# LCD.net
KiCad netlist of a schematic drawn in Altium Designer
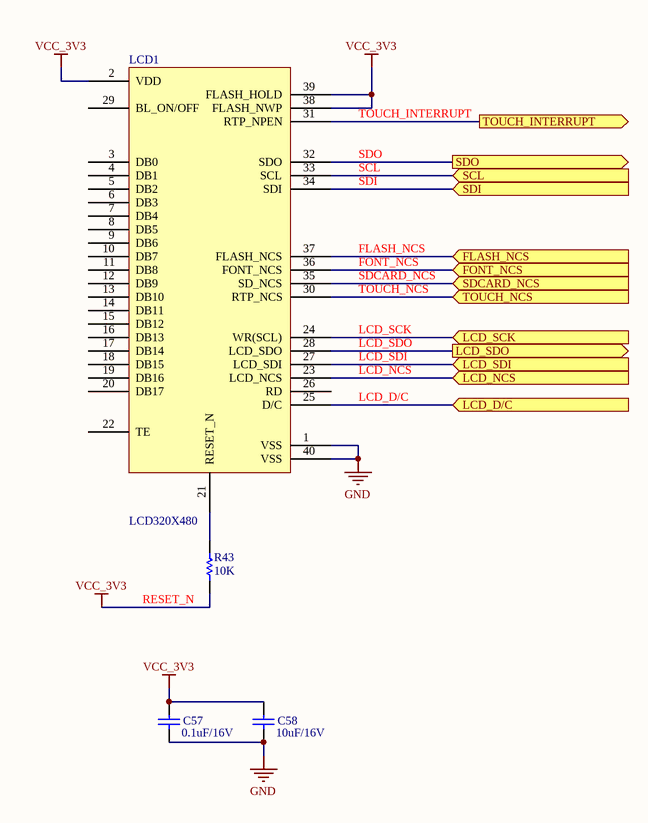
[diagram p0: LCD.SchDoc]

(export (version "E")
  (design (tool "Eeschema 10.0.6"))
  (components
    (comp (ref "C57")
      (value "0.1uF/16V")
      (footprint "RAD-0.3")
      (description "Capacitor")
      (fields (field (name "PUBLISHER") "Altium Limited"))
      (libsource (lib "Miscellaneous Devices") (part "Cap"))
    )
    (comp (ref "C58")
      (value "10uF/16V")
      (footprint "RAD-0.3")
      (description "Capacitor")
      (fields (field (name "PUBLISHER") "Altium Limited"))
      (libsource (lib "Miscellaneous Devices") (part "Cap"))
    )
    (comp (ref "LCD1") (value "LCD320X480") (libsource (lib "Schlib1") (part "ER-TFTM035-6")))
    (comp (ref "R43")
      (value "10K")
      (footprint "AXIAL-0.3")
      (description "Resistor")
      (fields (field (name "PUBLISHER") "Altium Limited"))
      (libsource (lib "Miscellaneous Devices") (part "Res1"))
    )
  )
  (nets
    (net (code "1") (name "/FLASH_NCS") (class "Default")
      (node (ref "LCD1") (pin "37") (pinfunction "FLASH_NCS_37") (pintype "passive"))
    )
    (net (code "2") (name "/FONT_NCS") (class "Default")
      (node (ref "LCD1") (pin "36") (pinfunction "FONT_NCS_36") (pintype "passive"))
    )
    (net (code "3") (name "/LCD_D{slash}C") (class "Default")
      (node (ref "LCD1") (pin "25") (pinfunction "D/C_25") (pintype "passive"))
    )
    (net (code "4") (name "/LCD_NCS") (class "Default")
      (node (ref "LCD1") (pin "23") (pinfunction "LCD_NCS_23") (pintype "passive"))
    )
    (net (code "5") (name "/LCD_SCK") (class "Default")
      (node (ref "LCD1") (pin "24") (pinfunction "WR(SCL)_24") (pintype "passive"))
    )
    (net (code "6") (name "/LCD_SDI") (class "Default")
      (node (ref "LCD1") (pin "27") (pinfunction "LCD_SDI_27") (pintype "passive"))
    )
    (net (code "7") (name "/LCD_SDO") (class "Default")
      (node (ref "LCD1") (pin "28") (pinfunction "LCD_SDO_28") (pintype "passive"))
    )
    (net (code "8") (name "/SCL") (class "Default")
      (node (ref "LCD1") (pin "33") (pinfunction "SCL_33") (pintype "passive"))
    )
    (net (code "9") (name "/SDCARD_NCS") (class "Default")
      (node (ref "LCD1") (pin "35") (pinfunction "SD_NCS_35") (pintype "passive"))
    )
    (net (code "10") (name "/SDI") (class "Default")
      (node (ref "LCD1") (pin "34") (pinfunction "SDI_34") (pintype "passive"))
    )
    (net (code "11") (name "/SDO") (class "Default")
      (node (ref "LCD1") (pin "32") (pinfunction "SDO_32") (pintype "passive"))
    )
    (net (code "12") (name "/TOUCH_INTERRUPT") (class "Default")
      (node (ref "LCD1") (pin "31") (pinfunction "RTP_NPEN_31") (pintype "passive"))
    )
    (net (code "13") (name "/TOUCH_NCS") (class "Default")
      (node (ref "LCD1") (pin "30") (pinfunction "RTP_NCS_30") (pintype "passive"))
    )
    (net (code "14") (name "GND") (class "Default")
      (node (ref "C57") (pin "1") (pinfunction "1_1") (pintype "passive"))
      (node (ref "C58") (pin "1") (pinfunction "1_1") (pintype "passive"))
      (node (ref "LCD1") (pin "1") (pinfunction "VSS_1") (pintype "passive"))
      (node (ref "LCD1") (pin "40") (pinfunction "VSS_40") (pintype "passive"))
    )
    (net (code "15") (name "Net-(LCD1-RESET_N)") (class "Default")
      (node (ref "LCD1") (pin "21") (pinfunction "RESET_N_21") (pintype "passive"))
      (node (ref "R43") (pin "2") (pinfunction "2_2") (pintype "passive"))
    )
    (net (code "16") (name "VCC_3V3") (class "Default")
      (node (ref "C57") (pin "2") (pinfunction "2_2") (pintype "passive"))
      (node (ref "C58") (pin "2") (pinfunction "2_2") (pintype "passive"))
      (node (ref "LCD1") (pin "2") (pinfunction "VDD_2") (pintype "passive"))
      (node (ref "LCD1") (pin "38") (pinfunction "FLASH_NWP_38") (pintype "passive"))
      (node (ref "LCD1") (pin "39") (pinfunction "FLASH_HOLD_39") (pintype "passive"))
      (node (ref "R43") (pin "1") (pinfunction "1_1") (pintype "passive"))
    )
    (net (code "17") (name "unconnected-(LCD1-BL_ON{slash}OFF-Pad29)") (class "Default")
      (node (ref "LCD1") (pin "29") (pinfunction "BL_ON/OFF_29") (pintype "passive"))
    )
    (net (code "18") (name "unconnected-(LCD1-DB0-Pad3)") (class "Default")
      (node (ref "LCD1") (pin "3") (pinfunction "DB0_3") (pintype "passive"))
    )
    (net (code "19") (name "unconnected-(LCD1-DB1-Pad4)") (class "Default")
      (node (ref "LCD1") (pin "4") (pinfunction "DB1_4") (pintype "passive"))
    )
    (net (code "20") (name "unconnected-(LCD1-DB2-Pad5)") (class "Default")
      (node (ref "LCD1") (pin "5") (pinfunction "DB2_5") (pintype "passive"))
    )
    (net (code "21") (name "unconnected-(LCD1-DB3-Pad6)") (class "Default")
      (node (ref "LCD1") (pin "6") (pinfunction "DB3_6") (pintype "passive"))
    )
    (net (code "22") (name "unconnected-(LCD1-DB4-Pad7)") (class "Default")
      (node (ref "LCD1") (pin "7") (pinfunction "DB4_7") (pintype "passive"))
    )
    (net (code "23") (name "unconnected-(LCD1-DB5-Pad8)") (class "Default")
      (node (ref "LCD1") (pin "8") (pinfunction "DB5_8") (pintype "passive"))
    )
    (net (code "24") (name "unconnected-(LCD1-DB6-Pad9)") (class "Default")
      (node (ref "LCD1") (pin "9") (pinfunction "DB6_9") (pintype "passive"))
    )
    (net (code "25") (name "unconnected-(LCD1-DB7-Pad10)") (class "Default")
      (node (ref "LCD1") (pin "10") (pinfunction "DB7_10") (pintype "passive"))
    )
    (net (code "26") (name "unconnected-(LCD1-DB8-Pad11)") (class "Default")
      (node (ref "LCD1") (pin "11") (pinfunction "DB8_11") (pintype "passive"))
    )
    (net (code "27") (name "unconnected-(LCD1-DB9-Pad12)") (class "Default")
      (node (ref "LCD1") (pin "12") (pinfunction "DB9_12") (pintype "passive"))
    )
    (net (code "28") (name "unconnected-(LCD1-DB10-Pad13)") (class "Default")
      (node (ref "LCD1") (pin "13") (pinfunction "DB10_13") (pintype "passive"))
    )
    (net (code "29") (name "unconnected-(LCD1-DB11-Pad14)") (class "Default")
      (node (ref "LCD1") (pin "14") (pinfunction "DB11_14") (pintype "passive"))
    )
    (net (code "30") (name "unconnected-(LCD1-DB12-Pad15)") (class "Default")
      (node (ref "LCD1") (pin "15") (pinfunction "DB12_15") (pintype "passive"))
    )
    (net (code "31") (name "unconnected-(LCD1-DB13-Pad16)") (class "Default")
      (node (ref "LCD1") (pin "16") (pinfunction "DB13_16") (pintype "passive"))
    )
    (net (code "32") (name "unconnected-(LCD1-DB14-Pad17)") (class "Default")
      (node (ref "LCD1") (pin "17") (pinfunction "DB14_17") (pintype "passive"))
    )
    (net (code "33") (name "unconnected-(LCD1-DB15-Pad18)") (class "Default")
      (node (ref "LCD1") (pin "18") (pinfunction "DB15_18") (pintype "passive"))
    )
    (net (code "34") (name "unconnected-(LCD1-DB16-Pad19)") (class "Default")
      (node (ref "LCD1") (pin "19") (pinfunction "DB16_19") (pintype "passive"))
    )
    (net (code "35") (name "unconnected-(LCD1-DB17-Pad20)") (class "Default")
      (node (ref "LCD1") (pin "20") (pinfunction "DB17_20") (pintype "passive"))
    )
    (net (code "36") (name "unconnected-(LCD1-RD-Pad26)") (class "Default")
      (node (ref "LCD1") (pin "26") (pinfunction "RD_26") (pintype "passive"))
    )
    (net (code "37") (name "unconnected-(LCD1-TE-Pad22)") (class "Default")
      (node (ref "LCD1") (pin "22") (pinfunction "TE_22") (pintype "passive"))
    )
  )
)
